# dnc_ext_info_bouton.net
KiCad netlist of a schematic drawn in EAGLE
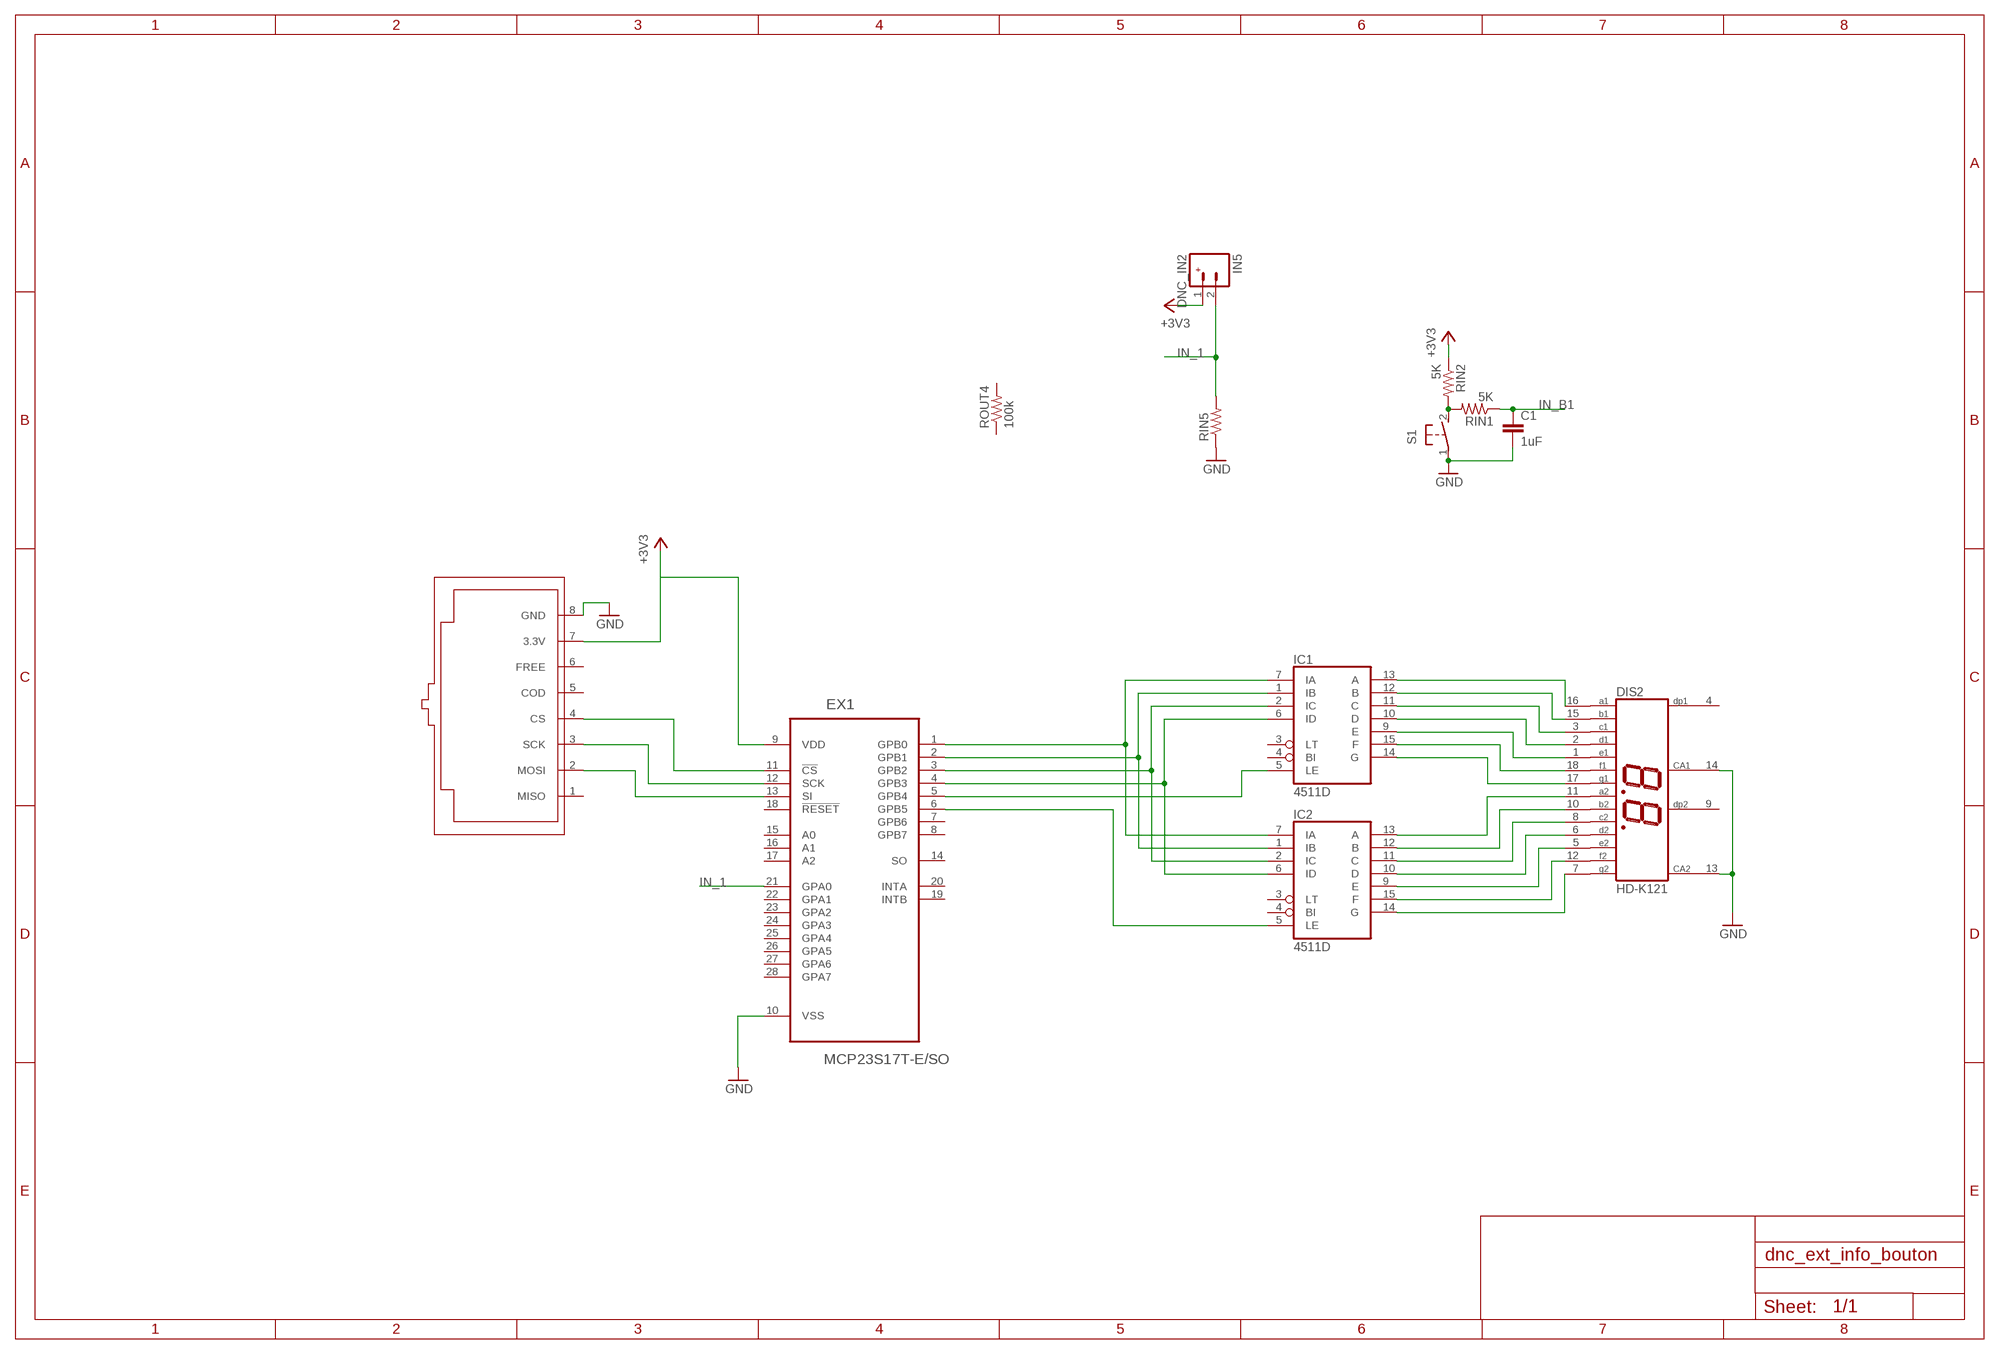
[diagram p0: schematic, sheet 1]

(export (version "E")
  (design (tool "Eeschema 10.0.6"))
  (components
    (comp (ref "C1")
      (value "1uF")
      (footprint "eagle-import:0603-CAP")
      (libsource (lib "eagle-import") (part "CAP0603-CAP"))
    )
    (comp (ref "DIS2")
      (value "HD-K121")
      (footprint "eagle-import:HDSP-R")
      (libsource (lib "eagle-import") (part "HD-K121"))
    )
    (comp (ref "EX1")
      (value "MCP23S17T-E/SO")
      (footprint "eagle-import:SOIC127P1030X265-28N")
      (libsource (lib "eagle-import") (part "MCP23S17T-E/SO"))
    )
    (comp (ref "IC1")
      (value "4511D")
      (footprint "eagle-import:SO16")
      (libsource (lib "eagle-import") (part "4511D"))
    )
    (comp (ref "IC2")
      (value "4511D")
      (footprint "eagle-import:SO16")
      (libsource (lib "eagle-import") (part "4511D"))
    )
    (comp (ref "IN5")
      (value "DNC_IN2")
      (footprint "eagle-import:DNC_IN2")
      (libsource (lib "eagle-import") (part "DNC_IN2"))
    )
    (comp (ref "RIN1")
      (value "5K")
      (footprint "eagle-import:0603-RES")
      (libsource (lib "eagle-import") (part "RESISTOR0603-RES"))
    )
    (comp (ref "RIN2")
      (value "5K")
      (footprint "eagle-import:0603-RES")
      (libsource (lib "eagle-import") (part "RESISTOR0603-RES"))
    )
    (comp (ref "RIN5")
      (value "RESISTOR0603-RES")
      (footprint "eagle-import:0603-RES")
      (libsource (lib "eagle-import") (part "RESISTOR0603-RES"))
    )
    (comp (ref "ROUT4")
      (value "100k")
      (footprint "eagle-import:0603-RES")
      (libsource (lib "eagle-import") (part "RESISTOR0603-RES"))
    )
    (comp (ref "S1")
      (value "31-XX")
      (footprint "eagle-import:B3F-31XX")
      (fields (field (name "MPN") "B3F-3100"))
      (libsource (lib "eagle-import") (part "31-XX"))
    )
    (comp (ref "U$6")
      (value "RJ45-EXTDNC")
      (footprint "eagle-import:RJ45-TRAFO")
      (libsource (lib "eagle-import") (part "RJ45-EXTDNC"))
    )
  )
  (nets
    (net (code "1") (name "+3V3") (class "Default")
      (node (ref "EX1") (pin "9") (pinfunction "VDD_9") (pintype "power_in"))
      (node (ref "IN5") (pin "1") (pinfunction "1_1") (pintype "passive"))
      (node (ref "RIN2") (pin "1") (pinfunction "1_1") (pintype "passive"))
      (node (ref "U$6") (pin "7") (pinfunction "3.3V_7") (pintype "power_in"))
    )
    (net (code "2") (name "/IN_1") (class "Default")
      (node (ref "EX1") (pin "21") (pinfunction "GPA0_21") (pintype "bidirectional"))
      (node (ref "IN5") (pin "2") (pinfunction "2_2") (pintype "passive"))
      (node (ref "RIN5") (pin "2") (pinfunction "2_2") (pintype "passive"))
    )
    (net (code "3") (name "/IN_B1") (class "Default")
      (node (ref "C1") (pin "1") (pinfunction "1_1") (pintype "passive"))
      (node (ref "RIN1") (pin "1") (pinfunction "1_1") (pintype "passive"))
    )
    (net (code "4") (name "GND") (class "Default")
      (node (ref "C1") (pin "2") (pinfunction "2_2") (pintype "passive"))
      (node (ref "DIS2") (pin "13") (pinfunction "CA2_13") (pintype "passive"))
      (node (ref "DIS2") (pin "14") (pinfunction "CA1_14") (pintype "passive"))
      (node (ref "EX1") (pin "10") (pinfunction "VSS_10") (pintype "passive"))
      (node (ref "RIN5") (pin "1") (pinfunction "1_1") (pintype "passive"))
      (node (ref "S1") (pin "1") (pinfunction "P_1") (pintype "passive"))
      (node (ref "U$6") (pin "8") (pinfunction "GND_8") (pintype "power_in"))
    )
    (net (code "5") (name "Net-(DIS2-A1)") (class "Default")
      (node (ref "DIS2") (pin "16") (pinfunction "A1_16") (pintype "passive"))
      (node (ref "IC1") (pin "13") (pinfunction "A_13") (pintype "output"))
    )
    (net (code "6") (name "Net-(DIS2-A2)") (class "Default")
      (node (ref "DIS2") (pin "11") (pinfunction "A2_11") (pintype "passive"))
      (node (ref "IC2") (pin "13") (pinfunction "A_13") (pintype "output"))
    )
    (net (code "7") (name "Net-(DIS2-B1)") (class "Default")
      (node (ref "DIS2") (pin "15") (pinfunction "B1_15") (pintype "passive"))
      (node (ref "IC1") (pin "12") (pinfunction "B_12") (pintype "output"))
    )
    (net (code "8") (name "Net-(DIS2-B2)") (class "Default")
      (node (ref "DIS2") (pin "10") (pinfunction "B2_10") (pintype "passive"))
      (node (ref "IC2") (pin "12") (pinfunction "B_12") (pintype "output"))
    )
    (net (code "9") (name "Net-(DIS2-C1)") (class "Default")
      (node (ref "DIS2") (pin "3") (pinfunction "C1_3") (pintype "passive"))
      (node (ref "IC1") (pin "11") (pinfunction "C_11") (pintype "output"))
    )
    (net (code "10") (name "Net-(DIS2-C2)") (class "Default")
      (node (ref "DIS2") (pin "8") (pinfunction "C2_8") (pintype "passive"))
      (node (ref "IC2") (pin "11") (pinfunction "C_11") (pintype "output"))
    )
    (net (code "11") (name "Net-(DIS2-D1)") (class "Default")
      (node (ref "DIS2") (pin "2") (pinfunction "D1_2") (pintype "passive"))
      (node (ref "IC1") (pin "10") (pinfunction "D_10") (pintype "output"))
    )
    (net (code "12") (name "Net-(DIS2-D2)") (class "Default")
      (node (ref "DIS2") (pin "6") (pinfunction "D2_6") (pintype "passive"))
      (node (ref "IC2") (pin "10") (pinfunction "D_10") (pintype "output"))
    )
    (net (code "13") (name "Net-(DIS2-E1)") (class "Default")
      (node (ref "DIS2") (pin "1") (pinfunction "E1_1") (pintype "passive"))
      (node (ref "IC1") (pin "9") (pinfunction "E_9") (pintype "output"))
    )
    (net (code "14") (name "Net-(DIS2-E2)") (class "Default")
      (node (ref "DIS2") (pin "5") (pinfunction "E2_5") (pintype "passive"))
      (node (ref "IC2") (pin "9") (pinfunction "E_9") (pintype "output"))
    )
    (net (code "15") (name "Net-(DIS2-F1)") (class "Default")
      (node (ref "DIS2") (pin "18") (pinfunction "F1_18") (pintype "passive"))
      (node (ref "IC1") (pin "15") (pinfunction "F_15") (pintype "output"))
    )
    (net (code "16") (name "Net-(DIS2-F2)") (class "Default")
      (node (ref "DIS2") (pin "12") (pinfunction "F2_12") (pintype "passive"))
      (node (ref "IC2") (pin "15") (pinfunction "F_15") (pintype "output"))
    )
    (net (code "17") (name "Net-(DIS2-G1)") (class "Default")
      (node (ref "DIS2") (pin "17") (pinfunction "G1_17") (pintype "passive"))
      (node (ref "IC1") (pin "14") (pinfunction "G_14") (pintype "output"))
    )
    (net (code "18") (name "Net-(DIS2-G2)") (class "Default")
      (node (ref "DIS2") (pin "7") (pinfunction "G2_7") (pintype "passive"))
      (node (ref "IC2") (pin "14") (pinfunction "G_14") (pintype "output"))
    )
    (net (code "19") (name "Net-(EX1-GPB0)") (class "Default")
      (node (ref "EX1") (pin "1") (pinfunction "GPB0_1") (pintype "bidirectional"))
      (node (ref "IC1") (pin "7") (pinfunction "IA_7") (pintype "input"))
      (node (ref "IC2") (pin "7") (pinfunction "IA_7") (pintype "input"))
    )
    (net (code "20") (name "Net-(EX1-GPB1)") (class "Default")
      (node (ref "EX1") (pin "2") (pinfunction "GPB1_2") (pintype "bidirectional"))
      (node (ref "IC1") (pin "1") (pinfunction "IB_1") (pintype "input"))
      (node (ref "IC2") (pin "1") (pinfunction "IB_1") (pintype "input"))
    )
    (net (code "21") (name "Net-(EX1-GPB2)") (class "Default")
      (node (ref "EX1") (pin "3") (pinfunction "GPB2_3") (pintype "bidirectional"))
      (node (ref "IC1") (pin "2") (pinfunction "IC_2") (pintype "input"))
      (node (ref "IC2") (pin "2") (pinfunction "IC_2") (pintype "input"))
    )
    (net (code "22") (name "Net-(EX1-GPB3)") (class "Default")
      (node (ref "EX1") (pin "4") (pinfunction "GPB3_4") (pintype "bidirectional"))
      (node (ref "IC1") (pin "6") (pinfunction "ID_6") (pintype "input"))
      (node (ref "IC2") (pin "6") (pinfunction "ID_6") (pintype "input"))
    )
    (net (code "23") (name "Net-(EX1-GPB4)") (class "Default")
      (node (ref "EX1") (pin "5") (pinfunction "GPB4_5") (pintype "bidirectional"))
      (node (ref "IC1") (pin "5") (pinfunction "LE_5") (pintype "input"))
    )
    (net (code "24") (name "Net-(EX1-GPB5)") (class "Default")
      (node (ref "EX1") (pin "6") (pinfunction "GPB5_6") (pintype "bidirectional"))
      (node (ref "IC2") (pin "5") (pinfunction "LE_5") (pintype "input"))
    )
    (net (code "25") (name "Net-(EX1-SCK)") (class "Default")
      (node (ref "EX1") (pin "12") (pinfunction "SCK_12") (pintype "input"))
      (node (ref "U$6") (pin "3") (pinfunction "SCK_3") (pintype "bidirectional"))
    )
    (net (code "26") (name "Net-(EX1-SI)") (class "Default")
      (node (ref "EX1") (pin "13") (pinfunction "SI_13") (pintype "input"))
      (node (ref "U$6") (pin "2") (pinfunction "MOSI_2") (pintype "bidirectional"))
    )
    (net (code "27") (name "Net-(EX1-~{CS})") (class "Default")
      (node (ref "EX1") (pin "11") (pinfunction "~{CS}_11") (pintype "input"))
      (node (ref "U$6") (pin "4") (pinfunction "CS_4") (pintype "bidirectional"))
    )
    (net (code "28") (name "Net-(S1-S)") (class "Default")
      (node (ref "RIN1") (pin "2") (pinfunction "2_2") (pintype "passive"))
      (node (ref "RIN2") (pin "2") (pinfunction "2_2") (pintype "passive"))
      (node (ref "S1") (pin "2") (pinfunction "S_2") (pintype "passive"))
    )
    (net (code "29") (name "unconnected-(DIS2-DP1-Pad4)") (class "Default")
      (node (ref "DIS2") (pin "4") (pinfunction "DP1_4") (pintype "passive"))
    )
    (net (code "30") (name "unconnected-(DIS2-DP2-Pad9)") (class "Default")
      (node (ref "DIS2") (pin "9") (pinfunction "DP2_9") (pintype "passive"))
    )
    (net (code "31") (name "unconnected-(EX1-A0-Pad15)") (class "Default")
      (node (ref "EX1") (pin "15") (pinfunction "A0_15") (pintype "input"))
    )
    (net (code "32") (name "unconnected-(EX1-A1-Pad16)") (class "Default")
      (node (ref "EX1") (pin "16") (pinfunction "A1_16") (pintype "input"))
    )
    (net (code "33") (name "unconnected-(EX1-A2-Pad17)") (class "Default")
      (node (ref "EX1") (pin "17") (pinfunction "A2_17") (pintype "input"))
    )
    (net (code "34") (name "unconnected-(EX1-GPA1-Pad22)") (class "Default")
      (node (ref "EX1") (pin "22") (pinfunction "GPA1_22") (pintype "bidirectional"))
    )
    (net (code "35") (name "unconnected-(EX1-GPA2-Pad23)") (class "Default")
      (node (ref "EX1") (pin "23") (pinfunction "GPA2_23") (pintype "bidirectional"))
    )
    (net (code "36") (name "unconnected-(EX1-GPA3-Pad24)") (class "Default")
      (node (ref "EX1") (pin "24") (pinfunction "GPA3_24") (pintype "bidirectional"))
    )
    (net (code "37") (name "unconnected-(EX1-GPA4-Pad25)") (class "Default")
      (node (ref "EX1") (pin "25") (pinfunction "GPA4_25") (pintype "bidirectional"))
    )
    (net (code "38") (name "unconnected-(EX1-GPA5-Pad26)") (class "Default")
      (node (ref "EX1") (pin "26") (pinfunction "GPA5_26") (pintype "bidirectional"))
    )
    (net (code "39") (name "unconnected-(EX1-GPA6-Pad27)") (class "Default")
      (node (ref "EX1") (pin "27") (pinfunction "GPA6_27") (pintype "bidirectional"))
    )
    (net (code "40") (name "unconnected-(EX1-GPA7-Pad28)") (class "Default")
      (node (ref "EX1") (pin "28") (pinfunction "GPA7_28") (pintype "bidirectional"))
    )
    (net (code "41") (name "unconnected-(EX1-GPB6-Pad7)") (class "Default")
      (node (ref "EX1") (pin "7") (pinfunction "GPB6_7") (pintype "bidirectional"))
    )
    (net (code "42") (name "unconnected-(EX1-GPB7-Pad8)") (class "Default")
      (node (ref "EX1") (pin "8") (pinfunction "GPB7_8") (pintype "bidirectional"))
    )
    (net (code "43") (name "unconnected-(EX1-INTA-Pad20)") (class "Default")
      (node (ref "EX1") (pin "20") (pinfunction "INTA_20") (pintype "output"))
    )
    (net (code "44") (name "unconnected-(EX1-INTB-Pad19)") (class "Default")
      (node (ref "EX1") (pin "19") (pinfunction "INTB_19") (pintype "output"))
    )
    (net (code "45") (name "unconnected-(EX1-SO-Pad14)") (class "Default")
      (node (ref "EX1") (pin "14") (pinfunction "SO_14") (pintype "output"))
    )
    (net (code "46") (name "unconnected-(EX1-~{RESET}-Pad18)") (class "Default")
      (node (ref "EX1") (pin "18") (pinfunction "~{RESET}_18") (pintype "input"))
    )
    (net (code "47") (name "unconnected-(IC1A-BI-Pad4)") (class "Default")
      (node (ref "IC1") (pin "4") (pinfunction "BI_4") (pintype "input"))
    )
    (net (code "48") (name "unconnected-(IC1A-LT-Pad3)") (class "Default")
      (node (ref "IC1") (pin "3") (pinfunction "LT_3") (pintype "input"))
    )
    (net (code "49") (name "unconnected-(IC2A-BI-Pad4)") (class "Default")
      (node (ref "IC2") (pin "4") (pinfunction "BI_4") (pintype "input"))
    )
    (net (code "50") (name "unconnected-(IC2A-LT-Pad3)") (class "Default")
      (node (ref "IC2") (pin "3") (pinfunction "LT_3") (pintype "input"))
    )
    (net (code "51") (name "unconnected-(ROUT4-Pad1)") (class "Default")
      (node (ref "ROUT4") (pin "1") (pinfunction "1_1") (pintype "passive"))
    )
    (net (code "52") (name "unconnected-(ROUT4-Pad2)") (class "Default")
      (node (ref "ROUT4") (pin "2") (pinfunction "2_2") (pintype "passive"))
    )
    (net (code "53") (name "unconnected-(U$6-COD-Pad5)") (class "Default")
      (node (ref "U$6") (pin "5") (pinfunction "COD_5") (pintype "bidirectional"))
    )
    (net (code "54") (name "unconnected-(U$6-FREE-Pad6)") (class "Default")
      (node (ref "U$6") (pin "6") (pinfunction "FREE_6") (pintype "no_connect"))
    )
    (net (code "55") (name "unconnected-(U$6-MISO-Pad1)") (class "Default")
      (node (ref "U$6") (pin "1") (pinfunction "MISO_1") (pintype "bidirectional"))
    )
  )
)
